# Input_channel.net
KiCad netlist of a schematic drawn in Altium Designer
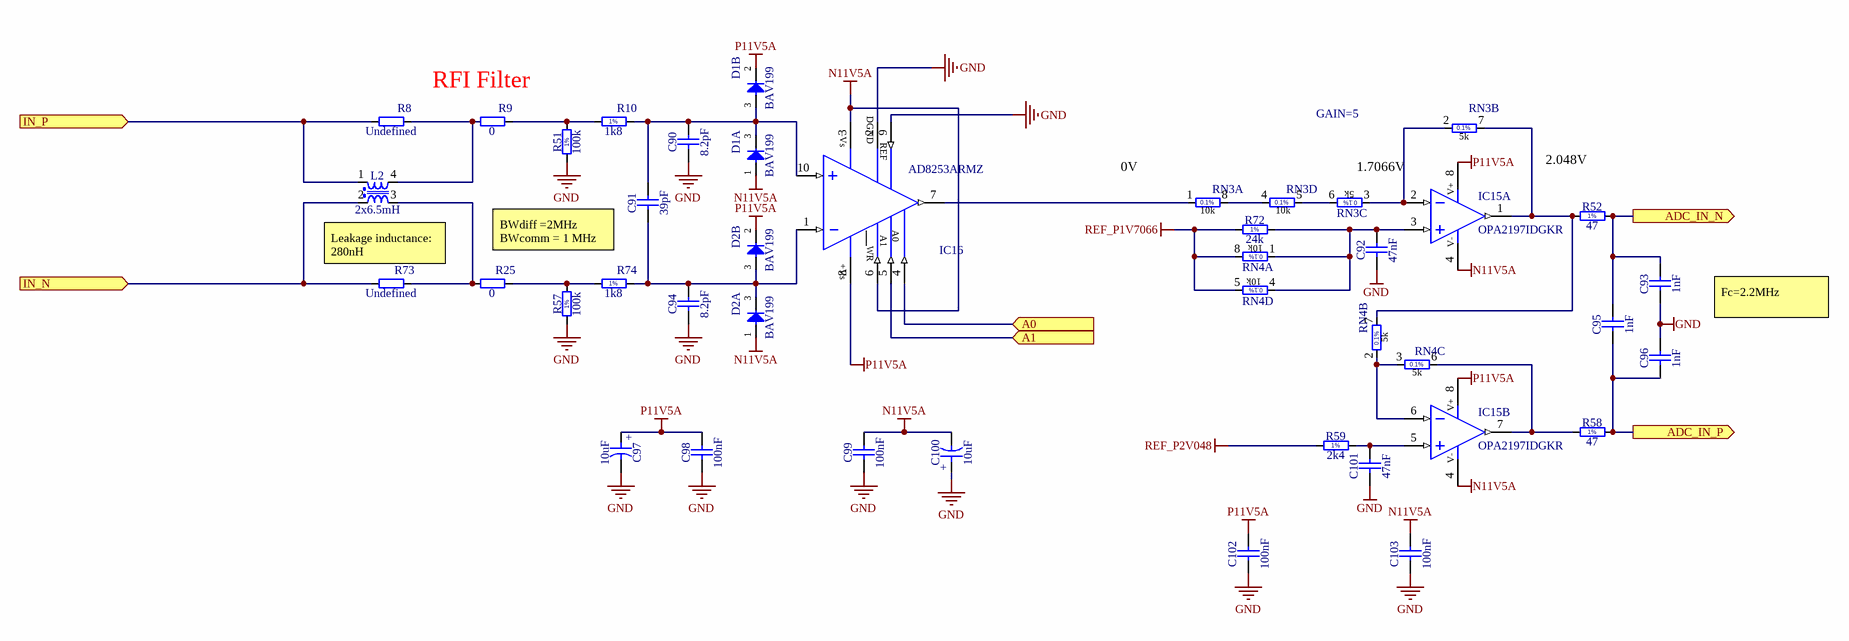
[diagram p0: Input_channel.SchDoc]

(export (version "E")
  (design (tool "Eeschema 10.0.6"))
  (components
    (comp (ref "C90")
      (value "8.2pF")
      (footprint "CAPC1608X87N")
      (description "Non-polarised capacitor")
      (fields
        (field (name "PART NUMBER") "CC0603_8.2PF_50V_0.5PF_NP0")
        (field (name "VOLTAGE") "50V")
        (field (name "AUTHOR") "CERN DEM JLC")
      )
      (libsource (lib "Capacitors") (part "Capacitor - non polarized"))
    )
    (comp (ref "C91")
      (value "39pF")
      (footprint "CAPC1608X87N")
      (description "Non-polarised capacitor")
      (fields
        (field (name "PART NUMBER") "CC0603_39PF_50V_5%_NP0")
        (field (name "VOLTAGE") "50V")
        (field (name "AUTHOR") "CERN DEM JLC")
      )
      (libsource (lib "Capacitors") (part "Capacitor - non polarized"))
    )
    (comp (ref "C92")
      (value "47nF")
      (footprint "CAPC2012X135N")
      (description "Non-polarised capacitor")
      (fields
        (field (name "PART NUMBER") "CC0805_47NF_25V_5%_C0G")
        (field (name "VOLTAGE") "25V")
        (field (name "AUTHOR") "CERN DEM JLC")
      )
      (libsource (lib "Capacitors") (part "Capacitor - non polarized"))
    )
    (comp (ref "C93")
      (value "1nF")
      (footprint "CAPC1608X90N")
      (description "Non-polarised capacitor")
      (fields
        (field (name "PART NUMBER") "CC0603_1NF_50V_1%_NP0")
        (field (name "VOLTAGE") "50V")
        (field (name "AUTHOR") "CERN DEM JLC")
      )
      (libsource (lib "Capacitors") (part "Capacitor - non polarized"))
    )
    (comp (ref "C94")
      (value "8.2pF")
      (footprint "CAPC1608X87N")
      (description "Non-polarised capacitor")
      (fields
        (field (name "PART NUMBER") "CC0603_8.2PF_50V_0.5PF_NP0")
        (field (name "VOLTAGE") "50V")
        (field (name "AUTHOR") "CERN DEM JLC")
      )
      (libsource (lib "Capacitors") (part "Capacitor - non polarized"))
    )
    (comp (ref "C95")
      (value "1nF")
      (footprint "CAPC1608X90N")
      (description "Non-polarised capacitor")
      (fields
        (field (name "PART NUMBER") "CC0603_1NF_50V_1%_NP0")
        (field (name "VOLTAGE") "50V")
        (field (name "AUTHOR") "CERN DEM JLC")
      )
      (libsource (lib "Capacitors") (part "Capacitor - non polarized"))
    )
    (comp (ref "C96")
      (value "1nF")
      (footprint "CAPC1608X90N")
      (description "Non-polarised capacitor")
      (fields
        (field (name "PART NUMBER") "CC0603_1NF_50V_1%_NP0")
        (field (name "VOLTAGE") "50V")
        (field (name "AUTHOR") "CERN DEM JLC")
      )
      (libsource (lib "Capacitors") (part "Capacitor - non polarized"))
    )
    (comp (ref "C97")
      (value "10uF")
      (footprint "CAPMP3216X180N")
      (description "Polarised capacitor")
      (fields
        (field (name "PART NUMBER") "CTE3216-18_10UF_16V_20%_AVX_TCJ")
        (field (name "VOLTAGE") "16V")
        (field (name "AUTHOR") "CERN DEM JLC")
      )
      (libsource (lib "Capacitors") (part "Capacitor - polarized"))
    )
    (comp (ref "C98")
      (value "100nF")
      (footprint "CAPC1005X55N")
      (description "Non-polarised capacitor")
      (fields
        (field (name "PART NUMBER") "CC0402_100NF_16V_10%_X7R")
        (field (name "VOLTAGE") "16V")
        (field (name "AUTHOR") "CERN DEM JLC")
      )
      (libsource (lib "Capacitors") (part "Capacitor - non polarized"))
    )
    (comp (ref "C99")
      (value "100nF")
      (footprint "CAPC1005X55N")
      (description "Non-polarised capacitor")
      (fields
        (field (name "PART NUMBER") "CC0402_100NF_16V_10%_X7R")
        (field (name "VOLTAGE") "16V")
        (field (name "AUTHOR") "CERN DEM JLC")
      )
      (libsource (lib "Capacitors") (part "Capacitor - non polarized"))
    )
    (comp (ref "C100")
      (value "10uF")
      (footprint "CAPMP3216X180N")
      (description "Polarised capacitor")
      (fields
        (field (name "PART NUMBER") "CTE3216-18_10UF_16V_20%_AVX_TCJ")
        (field (name "VOLTAGE") "16V")
        (field (name "AUTHOR") "CERN DEM JLC")
      )
      (libsource (lib "Capacitors") (part "Capacitor - polarized"))
    )
    (comp (ref "C101")
      (value "47nF")
      (footprint "CAPC2012X135N")
      (description "Non-polarised capacitor")
      (fields
        (field (name "PART NUMBER") "CC0805_47NF_25V_5%_C0G")
        (field (name "VOLTAGE") "25V")
        (field (name "AUTHOR") "CERN DEM JLC")
      )
      (libsource (lib "Capacitors") (part "Capacitor - non polarized"))
    )
    (comp (ref "C102")
      (value "100nF")
      (footprint "CAPC1005X55N")
      (description "Non-polarised capacitor")
      (fields
        (field (name "PART NUMBER") "CC0402_100NF_16V_10%_X7R")
        (field (name "VOLTAGE") "16V")
        (field (name "AUTHOR") "CERN DEM JLC")
      )
      (libsource (lib "Capacitors") (part "Capacitor - non polarized"))
    )
    (comp (ref "C103")
      (value "100nF")
      (footprint "CAPC1005X55N")
      (description "Non-polarised capacitor")
      (fields
        (field (name "PART NUMBER") "CC0402_100NF_16V_10%_X7R")
        (field (name "VOLTAGE") "16V")
        (field (name "AUTHOR") "CERN DEM JLC")
      )
      (libsource (lib "Capacitors") (part "Capacitor - non polarized"))
    )
    (comp (ref "D1")
      (value "BAV199")
      (footprint "SOT95P240X110-3N")
      (description "Serial Diode")
      (fields
        (field (name "VOLTAGE") "75V")
        (field (name "POWER") "250mW")
        (field (name "AUTHOR") "CERN DEM JMW")
      )
      (libsource (lib "ICs And Semiconductors") (part "Diode x2 A1C3_A3C2"))
    )
    (comp (ref "D2")
      (value "BAV199")
      (footprint "SOT95P240X110-3N")
      (description "Serial Diode")
      (fields
        (field (name "VOLTAGE") "75V")
        (field (name "POWER") "250mW")
        (field (name "AUTHOR") "CERN DEM JMW")
      )
      (libsource (lib "ICs And Semiconductors") (part "Diode x2 A1C3_A3C2"))
    )
    (comp (ref "IC15")
      (value "OPA2197IDGKR")
      (footprint "SOP65P490X110-8N")
      (description "36-V, Precision, Rail-to-Rail Input Output, Low Offset Voltage Op Amp 8-VSSOP")
      (fields (field (name "MANUFACTURER") "TEXAS INSTRUMENTS") (field (name "AUTHOR") "GK"))
      (libsource (lib "LIBRARY_SCH") (part "OA_OPA2197IDGKR"))
    )
    (comp (ref "IC16")
      (value "AD8253ARMZ")
      (footprint "SOP50P490X110-10N")
      (description "10MHz, 20V/us, G= 1, 10, 100, 1000 iCMOS Programmable Gain Instrumentation Amplifier")
      (fields (field (name "MANUFACTURER") "ANALOG DEVICES") (field (name "AUTHOR") "CERN DEM JLC"))
      (libsource (lib "ICs And Semiconductors") (part "AD8253"))
    )
    (comp (ref "L2")
      (value "2x6.5mH")
      (footprint "IND_WURTH_WE-SL2")
      (description "Inductor Common Mode")
      (fields
        (field (name "PART NUMBER") "IND_6.5MH_50%_WURTH_WE-SL2-744229")
        (field (name "POWER") "400mA")
        (field (name "AUTHOR") "CERN DEM JLC")
      )
      (libsource (lib "Inductors & Transformers") (part "Inductor Common Mode 1Dot-4 2Dot-3"))
    )
    (comp (ref "R8")
      (value "Undefined")
      (footprint "RESC1608X55N")
      (description "Resistor")
      (fields (field (name "PART NUMBER") "R0603_NO-VALUE") (field (name "AUTHOR") "CERN DEM JLC"))
      (libsource (lib "Resistors") (part "Resistor"))
    )
    (comp (ref "R9")
      (value "0")
      (footprint "RESC1608X55N")
      (description "Resistor")
      (fields
        (field (name "PART NUMBER") "R0603_0R_JUMPER")
        (field (name "MANUFACTURER") "GENERIC")
        (field (name "AUTHOR") "CERN DEM JLC")
      )
      (libsource (lib "Resistors") (part "Resistor"))
    )
    (comp (ref "R10")
      (value "1k8")
      (footprint "RESC1608X55N")
      (description "Resistor - 1%")
      (fields
        (field (name "PART NUMBER") "R0603_1K8_1%_0.1W_100PPM")
        (field (name "POWER") "0.1W")
        (field (name "AUTHOR") "CERN DEM JLC")
      )
      (libsource (lib "Resistors") (part "Resistor - 1%"))
    )
    (comp (ref "R25")
      (value "0")
      (footprint "RESC1608X55N")
      (description "Resistor")
      (fields
        (field (name "PART NUMBER") "R0603_0R_JUMPER")
        (field (name "MANUFACTURER") "GENERIC")
        (field (name "AUTHOR") "CERN DEM JLC")
      )
      (libsource (lib "Resistors") (part "Resistor"))
    )
    (comp (ref "R51")
      (value "100k")
      (footprint "RESC1608X55N")
      (description "Resistor - 1%")
      (fields
        (field (name "PART NUMBER") "R0603_100K_1%_0.1W_100PPM")
        (field (name "POWER") "0.1W")
        (field (name "AUTHOR") "CERN DEM JLC")
      )
      (libsource (lib "Resistors") (part "Resistor - 1%"))
    )
    (comp (ref "R52")
      (value "47")
      (footprint "RESC1005X40N")
      (description "Resistor - 1%")
      (fields
        (field (name "PART NUMBER") "R0402_47R_1%_0.0625W_100PPM")
        (field (name "POWER") "0.0625W")
        (field (name "AUTHOR") "CERN DEM JLC")
      )
      (libsource (lib "Resistors") (part "Resistor - 1%"))
    )
    (comp (ref "R57")
      (value "100k")
      (footprint "RESC1608X55N")
      (description "Resistor - 1%")
      (fields
        (field (name "PART NUMBER") "R0603_100K_1%_0.1W_100PPM")
        (field (name "POWER") "0.1W")
        (field (name "AUTHOR") "CERN DEM JLC")
      )
      (libsource (lib "Resistors") (part "Resistor - 1%"))
    )
    (comp (ref "R58")
      (value "47")
      (footprint "RESC1005X40N")
      (description "Resistor - 1%")
      (fields
        (field (name "PART NUMBER") "R0402_47R_1%_0.0625W_100PPM")
        (field (name "POWER") "0.0625W")
        (field (name "AUTHOR") "CERN DEM JLC")
      )
      (libsource (lib "Resistors") (part "Resistor - 1%"))
    )
    (comp (ref "R59")
      (value "2k4")
      (footprint "RESC1005X40N")
      (description "Resistor - 1%")
      (fields
        (field (name "PART NUMBER") "R0402_2K4_1%_0.0625W_100PPM")
        (field (name "POWER") "0.0625W")
        (field (name "AUTHOR") "CERN DEM JLC")
      )
      (libsource (lib "Resistors") (part "Resistor - 1%"))
    )
    (comp (ref "R72")
      (value "24k")
      (footprint "RESC1608X55N")
      (description "Resistor - 1%")
      (fields
        (field (name "PART NUMBER") "R0603_24K_1%_0.1W_100PPM")
        (field (name "POWER") "0.1W")
        (field (name "AUTHOR") "CERN DEM JLC")
      )
      (libsource (lib "Resistors") (part "Resistor - 1%"))
    )
    (comp (ref "R73")
      (value "Undefined")
      (footprint "RESC1608X55N")
      (description "Resistor")
      (fields (field (name "PART NUMBER") "R0603_NO-VALUE") (field (name "AUTHOR") "CERN DEM JLC"))
      (libsource (lib "Resistors") (part "Resistor"))
    )
    (comp (ref "R74")
      (value "1k8")
      (footprint "RESC1608X55N")
      (description "Resistor - 1%")
      (fields
        (field (name "PART NUMBER") "R0603_1K8_1%_0.1W_100PPM")
        (field (name "POWER") "0.1W")
        (field (name "AUTHOR") "CERN DEM JLC")
      )
      (libsource (lib "Resistors") (part "Resistor - 1%"))
    )
    (comp (ref "RN3")
      (value "10k 5K 5K 10K")
      (footprint "SOIC127P600X175-8N")
      (description "DIL8 Resistor Network 4 Resistors 10k-5k-5k-10k 0.1%")
      (fields
        (field (name "PART NUMBER") "RN_10K_5K_VISHAY_AORN2-1AT3")
        (field (name "POWER") "4x0.1W")
        (field (name "AUTHOR") "CERN DEM JLC")
      )
      (libsource (lib "Resistors") (part "RN DIL8_4xR_10k-5k-5k-10k_0.1%"))
    )
    (comp (ref "RN4")
      (value "10k 5K 5K 10K")
      (footprint "SOIC127P600X175-8N")
      (description "DIL8 Resistor Network 4 Resistors 10k-5k-5k-10k 0.1%")
      (fields
        (field (name "PART NUMBER") "RN_10K_5K_VISHAY_AORN2-1AT3")
        (field (name "POWER") "4x0.1W")
        (field (name "AUTHOR") "CERN DEM JLC")
      )
      (libsource (lib "Resistors") (part "RN DIL8_4xR_10k-5k-5k-10k_0.1%"))
    )
  )
  (nets
    (net (code "1") (name "/A0") (class "Default")
      (node (ref "IC16") (pin "4") (pinfunction "A0_4") (pintype "input"))
    )
    (net (code "2") (name "/A1") (class "Default")
      (node (ref "IC16") (pin "5") (pinfunction "A1_5") (pintype "input"))
    )
    (net (code "3") (name "/ADC_IN_N") (class "Default")
      (node (ref "C93") (pin "2") (pinfunction "2_2") (pintype "passive"))
      (node (ref "C95") (pin "2") (pinfunction "2_2") (pintype "passive"))
      (node (ref "R52") (pin "2") (pinfunction "2_2") (pintype "passive"))
    )
    (net (code "4") (name "/ADC_IN_P") (class "Default")
      (node (ref "C95") (pin "1") (pinfunction "1_1") (pintype "passive"))
      (node (ref "C96") (pin "1") (pinfunction "1_1") (pintype "passive"))
      (node (ref "R58") (pin "2") (pinfunction "2_2") (pintype "passive"))
    )
    (net (code "5") (name "/IN_N") (class "Default")
      (node (ref "L2") (pin "2") (pinfunction "2_2") (pintype "passive"))
      (node (ref "R73") (pin "1") (pinfunction "1_1") (pintype "passive"))
    )
    (net (code "6") (name "/IN_P") (class "Default")
      (node (ref "L2") (pin "1") (pinfunction "1_1") (pintype "passive"))
      (node (ref "R8") (pin "1") (pinfunction "1_1") (pintype "passive"))
    )
    (net (code "7") (name "GND") (class "Default")
      (node (ref "C100") (pin "1") (pinfunction "1_1") (pintype "passive"))
      (node (ref "C101") (pin "1") (pinfunction "1_1") (pintype "passive"))
      (node (ref "C102") (pin "1") (pinfunction "1_1") (pintype "passive"))
      (node (ref "C103") (pin "1") (pinfunction "1_1") (pintype "passive"))
      (node (ref "C90") (pin "1") (pinfunction "1_1") (pintype "passive"))
      (node (ref "C92") (pin "1") (pinfunction "1_1") (pintype "passive"))
      (node (ref "C93") (pin "1") (pinfunction "1_1") (pintype "passive"))
      (node (ref "C94") (pin "1") (pinfunction "1_1") (pintype "passive"))
      (node (ref "C96") (pin "2") (pinfunction "2_2") (pintype "passive"))
      (node (ref "C97") (pin "2") (pinfunction "2_2") (pintype "passive"))
      (node (ref "C98") (pin "1") (pinfunction "1_1") (pintype "passive"))
      (node (ref "C99") (pin "1") (pinfunction "1_1") (pintype "passive"))
      (node (ref "IC16") (pin "2") (pinfunction "DGND_2") (pintype "power_in"))
      (node (ref "IC16") (pin "9") (pinfunction "REF_9") (pintype "input"))
      (node (ref "R51") (pin "1") (pinfunction "1_1") (pintype "passive"))
      (node (ref "R57") (pin "1") (pinfunction "1_1") (pintype "passive"))
    )
    (net (code "8") (name "N11V5A") (class "Default")
      (node (ref "C100") (pin "2") (pinfunction "2_2") (pintype "passive"))
      (node (ref "C103") (pin "2") (pinfunction "2_2") (pintype "passive"))
      (node (ref "C99") (pin "2") (pinfunction "2_2") (pintype "passive"))
      (node (ref "D1") (pin "1") (pinfunction "A_1") (pintype "passive"))
      (node (ref "D2") (pin "1") (pinfunction "A_1") (pintype "passive"))
      (node (ref "IC15") (pin "4") (pinfunction "V-_4") (pintype "power_in"))
      (node (ref "IC16") (pin "3") (pinfunction "-VS_3") (pintype "power_in"))
      (node (ref "IC16") (pin "6") (pinfunction "~{WR}_6") (pintype "input"))
    )
    (net (code "9") (name "Net-(D1A-COMAC)") (class "Default")
      (node (ref "C90") (pin "2") (pinfunction "2_2") (pintype "passive"))
      (node (ref "C91") (pin "2") (pinfunction "2_2") (pintype "passive"))
      (node (ref "D1") (pin "3") (pinfunction "COMAC_3") (pintype "passive"))
      (node (ref "IC16") (pin "10") (pinfunction "+IN_10") (pintype "input"))
      (node (ref "R10") (pin "2") (pinfunction "2_2") (pintype "passive"))
    )
    (net (code "10") (name "Net-(D2A-COMAC)") (class "Default")
      (node (ref "C91") (pin "1") (pinfunction "1_1") (pintype "passive"))
      (node (ref "C94") (pin "2") (pinfunction "2_2") (pintype "passive"))
      (node (ref "D2") (pin "3") (pinfunction "COMAC_3") (pintype "passive"))
      (node (ref "IC16") (pin "1") (pinfunction "-IN_1") (pintype "input"))
      (node (ref "R74") (pin "2") (pinfunction "2_2") (pintype "passive"))
    )
    (net (code "11") (name "Net-(IC15A-IN+)") (class "Default")
      (node (ref "C92") (pin "2") (pinfunction "2_2") (pintype "passive"))
      (node (ref "IC15") (pin "3") (pinfunction "IN+_3") (pintype "input"))
      (node (ref "R72") (pin "2") (pinfunction "2_2") (pintype "passive"))
      (node (ref "RN4") (pin "1") (pinfunction "1_1") (pintype "passive"))
      (node (ref "RN4") (pin "4") (pinfunction "4_4") (pintype "passive"))
    )
    (net (code "12") (name "Net-(IC15A-IN-)") (class "Default")
      (node (ref "IC15") (pin "2") (pinfunction "IN-_2") (pintype "input"))
      (node (ref "RN3") (pin "2") (pinfunction "2_2") (pintype "passive"))
      (node (ref "RN3") (pin "3") (pinfunction "3_3") (pintype "passive"))
    )
    (net (code "13") (name "Net-(IC15A-OUT)") (class "Default")
      (node (ref "IC15") (pin "1") (pinfunction "OUT_1") (pintype "output"))
      (node (ref "R52") (pin "1") (pinfunction "1_1") (pintype "passive"))
      (node (ref "RN3") (pin "7") (pinfunction "7_7") (pintype "passive"))
      (node (ref "RN4") (pin "7") (pinfunction "7_7") (pintype "passive"))
    )
    (net (code "14") (name "Net-(IC15B-IN+)") (class "Default")
      (node (ref "C101") (pin "2") (pinfunction "2_2") (pintype "passive"))
      (node (ref "IC15") (pin "5") (pinfunction "IN+_5") (pintype "input"))
      (node (ref "R59") (pin "2") (pinfunction "2_2") (pintype "passive"))
    )
    (net (code "15") (name "Net-(IC15B-IN-)") (class "Default")
      (node (ref "IC15") (pin "6") (pinfunction "IN-_6") (pintype "input"))
      (node (ref "RN4") (pin "2") (pinfunction "2_2") (pintype "passive"))
      (node (ref "RN4") (pin "3") (pinfunction "3_3") (pintype "passive"))
    )
    (net (code "16") (name "Net-(IC15B-OUT)") (class "Default")
      (node (ref "IC15") (pin "7") (pinfunction "OUT_7") (pintype "output"))
      (node (ref "R58") (pin "1") (pinfunction "1_1") (pintype "passive"))
      (node (ref "RN4") (pin "6") (pinfunction "6_6") (pintype "passive"))
    )
    (net (code "17") (name "Net-(IC16-OUT)") (class "Default")
      (node (ref "IC16") (pin "7") (pinfunction "OUT_7") (pintype "output"))
      (node (ref "RN3") (pin "1") (pinfunction "1_1") (pintype "passive"))
    )
    (net (code "18") (name "Net-(L2-Pad3)") (class "Default")
      (node (ref "L2") (pin "3") (pinfunction "3_3") (pintype "passive"))
      (node (ref "R25") (pin "1") (pinfunction "1_1") (pintype "passive"))
      (node (ref "R73") (pin "2") (pinfunction "2_2") (pintype "passive"))
    )
    (net (code "19") (name "Net-(L2-Pad4)") (class "Default")
      (node (ref "L2") (pin "4") (pinfunction "4_4") (pintype "passive"))
      (node (ref "R8") (pin "2") (pinfunction "2_2") (pintype "passive"))
      (node (ref "R9") (pin "1") (pinfunction "1_1") (pintype "passive"))
    )
    (net (code "20") (name "Net-(R10-Pad1)") (class "Default")
      (node (ref "R10") (pin "1") (pinfunction "1_1") (pintype "passive"))
      (node (ref "R51") (pin "2") (pinfunction "2_2") (pintype "passive"))
      (node (ref "R9") (pin "2") (pinfunction "2_2") (pintype "passive"))
    )
    (net (code "21") (name "Net-(R25-Pad2)") (class "Default")
      (node (ref "R25") (pin "2") (pinfunction "2_2") (pintype "passive"))
      (node (ref "R57") (pin "2") (pinfunction "2_2") (pintype "passive"))
      (node (ref "R74") (pin "1") (pinfunction "1_1") (pintype "passive"))
    )
    (net (code "22") (name "Net-(RN3-Pad4)") (class "Default")
      (node (ref "RN3") (pin "4") (pinfunction "4_4") (pintype "passive"))
      (node (ref "RN3") (pin "8") (pinfunction "8_8") (pintype "passive"))
    )
    (net (code "23") (name "Net-(RN3-Pad5)") (class "Default")
      (node (ref "RN3") (pin "5") (pinfunction "5_5") (pintype "passive"))
      (node (ref "RN3") (pin "6") (pinfunction "6_6") (pintype "passive"))
    )
    (net (code "24") (name "P11V5A") (class "Default")
      (node (ref "C102") (pin "2") (pinfunction "2_2") (pintype "passive"))
      (node (ref "C97") (pin "1") (pinfunction "1_1") (pintype "passive"))
      (node (ref "C98") (pin "2") (pinfunction "2_2") (pintype "passive"))
      (node (ref "D1") (pin "2") (pinfunction "C_2") (pintype "passive"))
      (node (ref "D2") (pin "2") (pinfunction "C_2") (pintype "passive"))
      (node (ref "IC15") (pin "8") (pinfunction "V+_8") (pintype "power_in"))
      (node (ref "IC16") (pin "8") (pinfunction "+VS_8") (pintype "power_in"))
    )
    (net (code "25") (name "REF_P1V7066") (class "Default")
      (node (ref "R72") (pin "1") (pinfunction "1_1") (pintype "passive"))
      (node (ref "RN4") (pin "5") (pinfunction "5_5") (pintype "passive"))
      (node (ref "RN4") (pin "8") (pinfunction "8_8") (pintype "passive"))
    )
    (net (code "26") (name "REF_P2V048") (class "Default")
      (node (ref "R59") (pin "1") (pinfunction "1_1") (pintype "passive"))
    )
  )
)
